# evalboard_v2.net
KiCad netlist of a schematic drawn in EAGLE
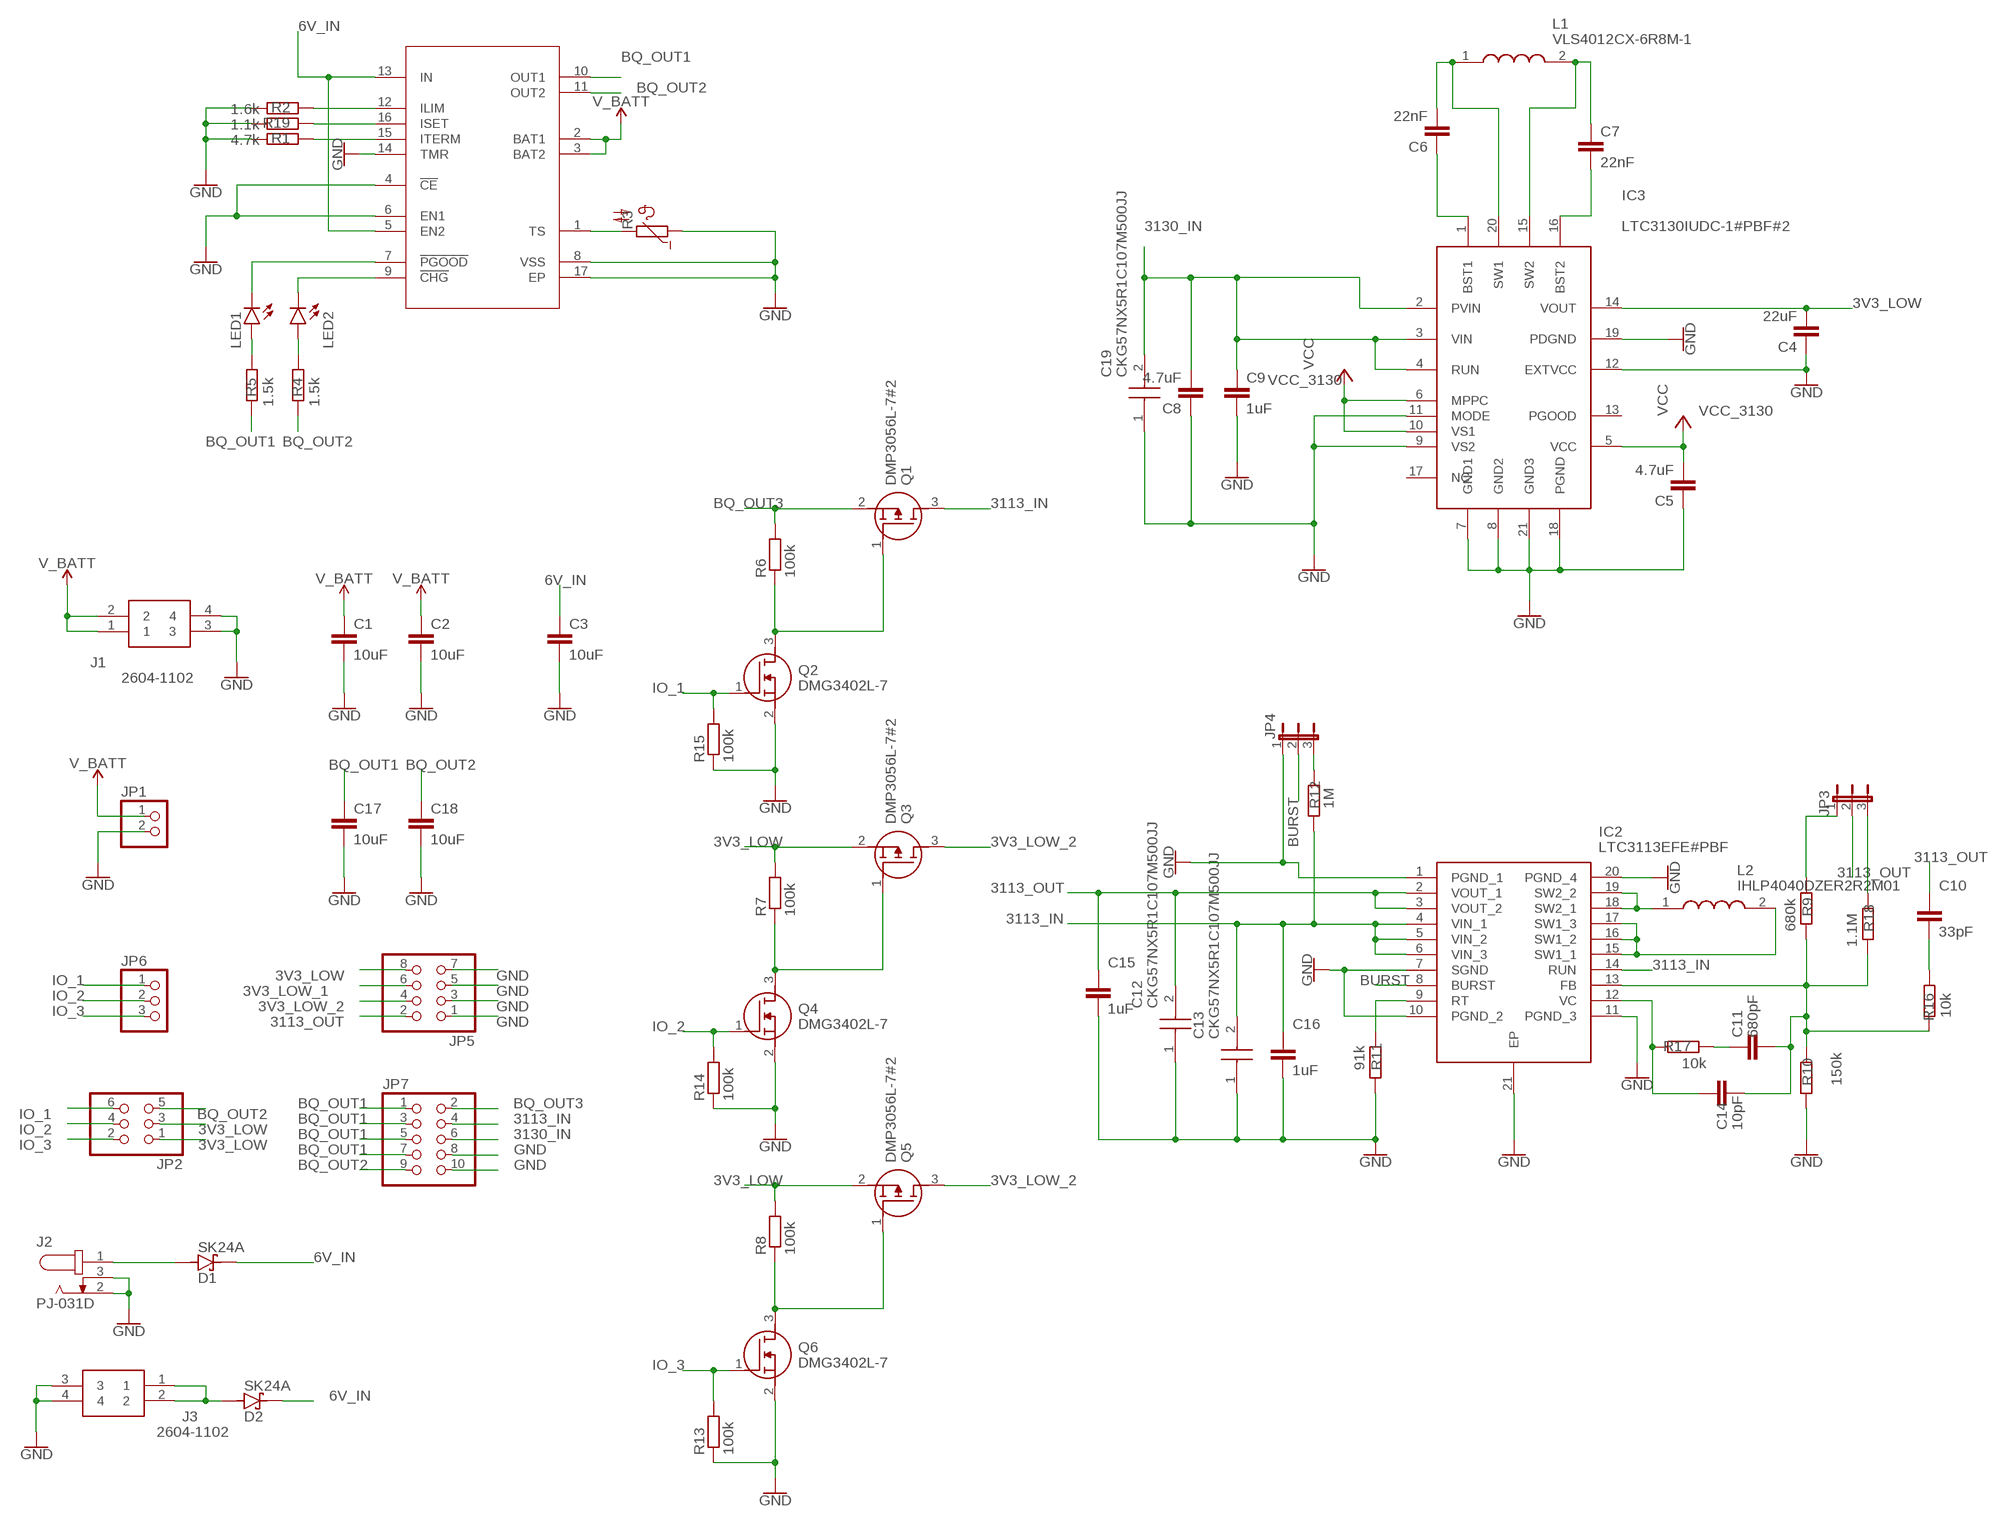
[diagram p0: schematic, sheet 1]

(export (version "E")
  (design (tool "Eeschema 10.0.6"))
  (components
    (comp (ref "C1")
      (value "10uF")
      (footprint "eagle-import:C1210")
      (libsource (lib "eagle-import") (part "C-EUC1210"))
    )
    (comp (ref "C2")
      (value "10uF")
      (footprint "eagle-import:C1210")
      (libsource (lib "eagle-import") (part "C-EUC1210"))
    )
    (comp (ref "C3")
      (value "10uF")
      (footprint "eagle-import:C1210")
      (libsource (lib "eagle-import") (part "C-EUC1210"))
    )
    (comp (ref "C4")
      (value "22uF")
      (footprint "eagle-import:C1210")
      (libsource (lib "eagle-import") (part "C-EUC1210"))
    )
    (comp (ref "C5")
      (value "4.7uF")
      (footprint "eagle-import:C1210")
      (libsource (lib "eagle-import") (part "C-EUC1210"))
    )
    (comp (ref "C6")
      (value "22nF")
      (footprint "eagle-import:C0603")
      (libsource (lib "eagle-import") (part "C-EUC0603"))
    )
    (comp (ref "C7")
      (value "22nF")
      (footprint "eagle-import:C0603")
      (libsource (lib "eagle-import") (part "C-EUC0603"))
    )
    (comp (ref "C8")
      (value "4.7uF")
      (footprint "eagle-import:C1210")
      (libsource (lib "eagle-import") (part "C-EUC1210"))
    )
    (comp (ref "C9")
      (value "1uF")
      (footprint "eagle-import:C0603")
      (libsource (lib "eagle-import") (part "C-EUC0603"))
    )
    (comp (ref "C10")
      (value "33pF")
      (footprint "eagle-import:C0603")
      (libsource (lib "eagle-import") (part "C-EUC0603"))
    )
    (comp (ref "C11")
      (value "680pF")
      (footprint "eagle-import:C0603")
      (libsource (lib "eagle-import") (part "C-EUC0603"))
    )
    (comp (ref "C12")
      (value "CKG57NX5R1C107M500JJ")
      (footprint "eagle-import:CAPC6050X550N")
      (fields (field (name "MOUSER_PART_NUMBER") "810-CKG57NX5R1C107MJ"))
      (libsource (lib "eagle-import") (part "CKG57NX5R1C107M500JJ"))
    )
    (comp (ref "C13")
      (value "CKG57NX5R1C107M500JJ")
      (footprint "eagle-import:CAPC6050X550N")
      (fields (field (name "MOUSER_PART_NUMBER") "810-CKG57NX5R1C107MJ"))
      (libsource (lib "eagle-import") (part "CKG57NX5R1C107M500JJ"))
    )
    (comp (ref "C14")
      (value "10pF")
      (footprint "eagle-import:C0603")
      (libsource (lib "eagle-import") (part "C-EUC0603"))
    )
    (comp (ref "C15")
      (value "1uF")
      (footprint "eagle-import:C0603")
      (libsource (lib "eagle-import") (part "C-EUC0603"))
    )
    (comp (ref "C16")
      (value "1uF")
      (footprint "eagle-import:C0603")
      (libsource (lib "eagle-import") (part "C-EUC0603"))
    )
    (comp (ref "C17")
      (value "10uF")
      (footprint "eagle-import:C1210")
      (libsource (lib "eagle-import") (part "C-EUC1210"))
    )
    (comp (ref "C18")
      (value "10uF")
      (footprint "eagle-import:C1210")
      (libsource (lib "eagle-import") (part "C-EUC1210"))
    )
    (comp (ref "C19")
      (value "CKG57NX5R1C107M500JJ")
      (footprint "eagle-import:CAPC6050X550N")
      (fields (field (name "MOUSER_PART_NUMBER") "810-CKG57NX5R1C107MJ"))
      (libsource (lib "eagle-import") (part "CKG57NX5R1C107M500JJ"))
    )
    (comp (ref "D1")
      (value "SK24A")
      (footprint "eagle-import:DIOM4325X250N")
      (fields (field (name "DIGI-KEY_PART_NUMBER") "1655-SK24ATR-ND") (field (name "MF") "SMC Diode"))
      (libsource (lib "eagle-import") (part "SK24A"))
    )
    (comp (ref "D2")
      (value "SK24A")
      (footprint "eagle-import:DIOM4325X250N")
      (fields (field (name "DIGI-KEY_PART_NUMBER") "1655-SK24ATR-ND") (field (name "MF") "SMC Diode"))
      (libsource (lib "eagle-import") (part "SK24A"))
    )
    (comp (ref "IC1")
      (value "BQ24074")
      (footprint "eagle-import:QFN50P300X300X100-17N")
      (libsource (lib "eagle-import") (part "BQ24074"))
    )
    (comp (ref "IC2")
      (value "LTC3113EFE#PBF")
      (footprint "eagle-import:SOP65P640X120-21N")
      (fields (field (name "MOUSER_PART_NUMBER") "584-LTC3113EFE#PBF"))
      (libsource (lib "eagle-import") (part "LTC3113EFE#PBF"))
    )
    (comp (ref "IC3")
      (value "LTC3130IUDC-1#PBF#2")
      (footprint "eagle-import:QFN50P300X400X80-21N")
      (fields (field (name "MANUFACTURER_PART_NUMBER") "LTC3130IUDC-1#PBF"))
      (libsource (lib "eagle-import") (part "LTC3130IUDC-1#PBF#2"))
    )
    (comp (ref "J1")
      (value "2604-1102")
      (footprint "eagle-import:26041102")
      (libsource (lib "eagle-import") (part "2604-1102"))
    )
    (comp (ref "J2")
      (value "PJ-031D")
      (footprint "eagle-import:CUI_PJ-031D")
      (fields (field (name "MF") "CUI Devices"))
      (libsource (lib "eagle-import") (part "PJ-031D"))
    )
    (comp (ref "J3")
      (value "2604-1102")
      (footprint "eagle-import:26041102")
      (libsource (lib "eagle-import") (part "2604-1102"))
    )
    (comp (ref "JP1")
      (value "PINHD-1X2")
      (footprint "eagle-import:1X02")
      (libsource (lib "eagle-import") (part "PINHD-1X2"))
    )
    (comp (ref "JP2")
      (value "PINHD-2X3")
      (footprint "eagle-import:2X03")
      (libsource (lib "eagle-import") (part "PINHD-2X3"))
    )
    (comp (ref "JP3")
      (value "JP2E")
      (footprint "eagle-import:JP2")
      (libsource (lib "eagle-import") (part "JP2E"))
    )
    (comp (ref "JP4")
      (value "JP2E")
      (footprint "eagle-import:JP2")
      (libsource (lib "eagle-import") (part "JP2E"))
    )
    (comp (ref "JP5")
      (value "PINHD-2X4")
      (footprint "eagle-import:2X04")
      (libsource (lib "eagle-import") (part "PINHD-2X4"))
    )
    (comp (ref "JP6")
      (value "PINHD-1X3")
      (footprint "eagle-import:1X03")
      (libsource (lib "eagle-import") (part "PINHD-1X3"))
    )
    (comp (ref "JP7")
      (value "PINHD-2X5")
      (footprint "eagle-import:2X05")
      (libsource (lib "eagle-import") (part "PINHD-2X5"))
    )
    (comp (ref "L1")
      (value "VLS4012CX-6R8M-1")
      (footprint "eagle-import:VLS4012")
      (libsource (lib "eagle-import") (part "VLS4012CX-6R8M-1"))
    )
    (comp (ref "L2")
      (value "IHLP4040DZER2R2M01")
      (footprint "eagle-import:INDPM108102X400N")
      (fields (field (name "MOUSER_PART_NUMBER") "70-IHLP4040DZER2R2M0"))
      (libsource (lib "eagle-import") (part "IHLP4040DZER2R2M01"))
    )
    (comp (ref "LED1")
      (value "LEDCHIP-LED0603")
      (footprint "eagle-import:CHIP-LED0603")
      (libsource (lib "eagle-import") (part "LEDCHIP-LED0603"))
    )
    (comp (ref "LED2")
      (value "LEDCHIP-LED0603")
      (footprint "eagle-import:CHIP-LED0603")
      (libsource (lib "eagle-import") (part "LEDCHIP-LED0603"))
    )
    (comp (ref "Q1")
      (value "DMP3056L-7#2")
      (footprint "eagle-import:SOT96P240X100-3N")
      (fields
        (field (name "ARROW_PART_NUMBER") "DMP3056L-7")
        (field (name "MOUSER_PART_NUMBER") "621-DMP3056L-7")
      )
      (libsource (lib "eagle-import") (part "DMP3056L-7#2"))
    )
    (comp (ref "Q2")
      (value "DMG3402L-7")
      (footprint "eagle-import:SOT96P240X110-3N")
      (fields (field (name "MOUSER_PART_NUMBER") "621-DMG3402L-7"))
      (libsource (lib "eagle-import") (part "DMG3402L-7"))
    )
    (comp (ref "Q3")
      (value "DMP3056L-7#2")
      (footprint "eagle-import:SOT96P240X100-3N")
      (fields
        (field (name "ARROW_PART_NUMBER") "DMP3056L-7")
        (field (name "MOUSER_PART_NUMBER") "621-DMP3056L-7")
      )
      (libsource (lib "eagle-import") (part "DMP3056L-7#2"))
    )
    (comp (ref "Q4")
      (value "DMG3402L-7")
      (footprint "eagle-import:SOT96P240X110-3N")
      (fields (field (name "MOUSER_PART_NUMBER") "621-DMG3402L-7"))
      (libsource (lib "eagle-import") (part "DMG3402L-7"))
    )
    (comp (ref "Q5")
      (value "DMP3056L-7#2")
      (footprint "eagle-import:SOT96P240X100-3N")
      (fields
        (field (name "ARROW_PART_NUMBER") "DMP3056L-7")
        (field (name "MOUSER_PART_NUMBER") "621-DMP3056L-7")
      )
      (libsource (lib "eagle-import") (part "DMP3056L-7#2"))
    )
    (comp (ref "Q6")
      (value "DMG3402L-7")
      (footprint "eagle-import:SOT96P240X110-3N")
      (fields (field (name "MOUSER_PART_NUMBER") "621-DMG3402L-7"))
      (libsource (lib "eagle-import") (part "DMG3402L-7"))
    )
    (comp (ref "R1")
      (value "4.7k")
      (footprint "eagle-import:R0603")
      (libsource (lib "eagle-import") (part "R-EU_R0603"))
    )
    (comp (ref "R2")
      (value "1.6k")
      (footprint "eagle-import:R0603")
      (libsource (lib "eagle-import") (part "R-EU_R0603"))
    )
    (comp (ref "R3")
      (value "10k")
      (footprint "eagle-import:P640")
      (libsource (lib "eagle-import") (part "NTC640"))
    )
    (comp (ref "R4")
      (value "1.5k")
      (footprint "eagle-import:R0603")
      (libsource (lib "eagle-import") (part "R-EU_R0603"))
    )
    (comp (ref "R5")
      (value "1.5k")
      (footprint "eagle-import:R0603")
      (libsource (lib "eagle-import") (part "R-EU_R0603"))
    )
    (comp (ref "R6")
      (value "100k")
      (footprint "eagle-import:R0603")
      (libsource (lib "eagle-import") (part "R-EU_R0603"))
    )
    (comp (ref "R7")
      (value "100k")
      (footprint "eagle-import:R0603")
      (libsource (lib "eagle-import") (part "R-EU_R0603"))
    )
    (comp (ref "R8")
      (value "100k")
      (footprint "eagle-import:R0603")
      (libsource (lib "eagle-import") (part "R-EU_R0603"))
    )
    (comp (ref "R9")
      (value "680k")
      (footprint "eagle-import:R0603")
      (libsource (lib "eagle-import") (part "R-EU_R0603"))
    )
    (comp (ref "R10")
      (value "150k")
      (footprint "eagle-import:R0603")
      (libsource (lib "eagle-import") (part "R-EU_R0603"))
    )
    (comp (ref "R11")
      (value "91k")
      (footprint "eagle-import:R0603")
      (libsource (lib "eagle-import") (part "R-EU_R0603"))
    )
    (comp (ref "R12")
      (value "1M")
      (footprint "eagle-import:R0603")
      (libsource (lib "eagle-import") (part "R-EU_R0603"))
    )
    (comp (ref "R13")
      (value "100k")
      (footprint "eagle-import:R0603")
      (libsource (lib "eagle-import") (part "R-EU_R0603"))
    )
    (comp (ref "R14")
      (value "100k")
      (footprint "eagle-import:R0603")
      (libsource (lib "eagle-import") (part "R-EU_R0603"))
    )
    (comp (ref "R15")
      (value "100k")
      (footprint "eagle-import:R0603")
      (libsource (lib "eagle-import") (part "R-EU_R0603"))
    )
    (comp (ref "R16")
      (value "10k")
      (footprint "eagle-import:R0603")
      (libsource (lib "eagle-import") (part "R-EU_R0603"))
    )
    (comp (ref "R17")
      (value "10k")
      (footprint "eagle-import:R0603")
      (libsource (lib "eagle-import") (part "R-EU_R0603"))
    )
    (comp (ref "R18")
      (value "1.1M")
      (footprint "eagle-import:R0603")
      (libsource (lib "eagle-import") (part "R-EU_R0603"))
    )
    (comp (ref "R19")
      (value "1.1k")
      (footprint "eagle-import:R0603")
      (libsource (lib "eagle-import") (part "R-EU_R0603"))
    )
  )
  (nets
    (net (code "1") (name "/3V3_LOW") (class "Default")
      (node (ref "C4") (pin "2") (pinfunction "2_2") (pintype "passive"))
      (node (ref "IC3") (pin "14") (pinfunction "VOUT_14") (pintype "output"))
      (node (ref "JP2") (pin "1") (pinfunction "1_1") (pintype "passive"))
      (node (ref "JP2") (pin "3") (pinfunction "3_3") (pintype "passive"))
      (node (ref "JP5") (pin "8") (pinfunction "8_8") (pintype "passive"))
      (node (ref "Q3") (pin "2") (pinfunction "S_2") (pintype "bidirectional"))
      (node (ref "Q5") (pin "2") (pinfunction "S_2") (pintype "bidirectional"))
      (node (ref "R7") (pin "2") (pinfunction "2_2") (pintype "passive"))
      (node (ref "R8") (pin "2") (pinfunction "2_2") (pintype "passive"))
    )
    (net (code "2") (name "/3V3_LOW_1") (class "Default")
      (node (ref "JP5") (pin "6") (pinfunction "6_6") (pintype "passive"))
    )
    (net (code "3") (name "/3V3_LOW_2") (class "Default")
      (node (ref "JP5") (pin "4") (pinfunction "4_4") (pintype "passive"))
      (node (ref "Q3") (pin "3") (pinfunction "D_3") (pintype "bidirectional"))
      (node (ref "Q5") (pin "3") (pinfunction "D_3") (pintype "bidirectional"))
    )
    (net (code "4") (name "/6V_IN") (class "Default")
      (node (ref "C3") (pin "1") (pinfunction "1_1") (pintype "passive"))
      (node (ref "D1") (pin "C") (pinfunction "K_C") (pintype "passive"))
      (node (ref "D2") (pin "C") (pinfunction "K_C") (pintype "passive"))
      (node (ref "IC1") (pin "13") (pinfunction "IN_13") (pintype "bidirectional"))
      (node (ref "IC1") (pin "5") (pinfunction "EN2_5") (pintype "bidirectional"))
    )
    (net (code "5") (name "/3113_IN") (class "Default")
      (node (ref "C13") (pin "2") (pinfunction "2_2") (pintype "bidirectional"))
      (node (ref "C16") (pin "1") (pinfunction "1_1") (pintype "passive"))
      (node (ref "IC2") (pin "14") (pinfunction "RUN_14") (pintype "bidirectional"))
      (node (ref "IC2") (pin "4") (pinfunction "VIN_1_4") (pintype "bidirectional"))
      (node (ref "IC2") (pin "5") (pinfunction "VIN_2_5") (pintype "bidirectional"))
      (node (ref "IC2") (pin "6") (pinfunction "VIN_3_6") (pintype "bidirectional"))
      (node (ref "JP7") (pin "4") (pinfunction "4_4") (pintype "passive"))
      (node (ref "Q1") (pin "3") (pinfunction "D_3") (pintype "bidirectional"))
      (node (ref "R12") (pin "1") (pinfunction "1_1") (pintype "passive"))
    )
    (net (code "6") (name "/3113_OUT") (class "Default")
      (node (ref "C10") (pin "1") (pinfunction "1_1") (pintype "passive"))
      (node (ref "C12") (pin "2") (pinfunction "2_2") (pintype "bidirectional"))
      (node (ref "C15") (pin "1") (pinfunction "1_1") (pintype "passive"))
      (node (ref "IC2") (pin "2") (pinfunction "VOUT_1_2") (pintype "bidirectional"))
      (node (ref "IC2") (pin "3") (pinfunction "VOUT_2_3") (pintype "bidirectional"))
      (node (ref "JP3") (pin "2") (pinfunction "2_2") (pintype "passive"))
      (node (ref "JP5") (pin "2") (pinfunction "2_2") (pintype "passive"))
    )
    (net (code "7") (name "/3130_IN") (class "Default")
      (node (ref "C19") (pin "2") (pinfunction "2_2") (pintype "bidirectional"))
      (node (ref "C8") (pin "2") (pinfunction "2_2") (pintype "passive"))
      (node (ref "C9") (pin "1") (pinfunction "1_1") (pintype "passive"))
      (node (ref "IC3") (pin "2") (pinfunction "PVIN_2") (pintype "input"))
      (node (ref "IC3") (pin "3") (pinfunction "VIN_3") (pintype "input"))
      (node (ref "IC3") (pin "4") (pinfunction "RUN_4") (pintype "bidirectional"))
      (node (ref "JP7") (pin "6") (pinfunction "6_6") (pintype "passive"))
    )
    (net (code "8") (name "/BQ_OUT1") (class "Default")
      (node (ref "C17") (pin "1") (pinfunction "1_1") (pintype "passive"))
      (node (ref "IC1") (pin "10") (pinfunction "OUT1_10") (pintype "bidirectional"))
      (node (ref "JP7") (pin "1") (pinfunction "1_1") (pintype "passive"))
      (node (ref "JP7") (pin "3") (pinfunction "3_3") (pintype "passive"))
      (node (ref "JP7") (pin "5") (pinfunction "5_5") (pintype "passive"))
      (node (ref "JP7") (pin "7") (pinfunction "7_7") (pintype "passive"))
      (node (ref "R5") (pin "2") (pinfunction "2_2") (pintype "passive"))
    )
    (net (code "9") (name "/BQ_OUT2") (class "Default")
      (node (ref "C18") (pin "1") (pinfunction "1_1") (pintype "passive"))
      (node (ref "IC1") (pin "11") (pinfunction "OUT2_11") (pintype "bidirectional"))
      (node (ref "JP2") (pin "5") (pinfunction "5_5") (pintype "passive"))
      (node (ref "JP7") (pin "9") (pinfunction "9_9") (pintype "passive"))
      (node (ref "R4") (pin "2") (pinfunction "2_2") (pintype "passive"))
    )
    (net (code "10") (name "/BQ_OUT3") (class "Default")
      (node (ref "JP7") (pin "2") (pinfunction "2_2") (pintype "passive"))
      (node (ref "Q1") (pin "2") (pinfunction "S_2") (pintype "bidirectional"))
      (node (ref "R6") (pin "2") (pinfunction "2_2") (pintype "passive"))
    )
    (net (code "11") (name "/BURST") (class "Default")
      (node (ref "IC2") (pin "8") (pinfunction "BURST_8") (pintype "bidirectional"))
      (node (ref "JP4") (pin "2") (pinfunction "2_2") (pintype "passive"))
    )
    (net (code "12") (name "/IO_1") (class "Default")
      (node (ref "JP2") (pin "6") (pinfunction "6_6") (pintype "passive"))
      (node (ref "JP6") (pin "1") (pinfunction "1_1") (pintype "passive"))
      (node (ref "Q2") (pin "1") (pinfunction "G_1") (pintype "bidirectional"))
      (node (ref "R15") (pin "2") (pinfunction "2_2") (pintype "passive"))
    )
    (net (code "13") (name "/IO_2") (class "Default")
      (node (ref "JP2") (pin "4") (pinfunction "4_4") (pintype "passive"))
      (node (ref "JP6") (pin "2") (pinfunction "2_2") (pintype "passive"))
      (node (ref "Q4") (pin "1") (pinfunction "G_1") (pintype "bidirectional"))
      (node (ref "R14") (pin "2") (pinfunction "2_2") (pintype "passive"))
    )
    (net (code "14") (name "/IO_3") (class "Default")
      (node (ref "JP2") (pin "2") (pinfunction "2_2") (pintype "passive"))
      (node (ref "JP6") (pin "3") (pinfunction "3_3") (pintype "passive"))
      (node (ref "Q6") (pin "1") (pinfunction "G_1") (pintype "bidirectional"))
      (node (ref "R13") (pin "2") (pinfunction "2_2") (pintype "passive"))
    )
    (net (code "15") (name "GND") (class "Default")
      (node (ref "C1") (pin "2") (pinfunction "2_2") (pintype "passive"))
      (node (ref "C12") (pin "1") (pinfunction "1_1") (pintype "bidirectional"))
      (node (ref "C13") (pin "1") (pinfunction "1_1") (pintype "bidirectional"))
      (node (ref "C15") (pin "2") (pinfunction "2_2") (pintype "passive"))
      (node (ref "C16") (pin "2") (pinfunction "2_2") (pintype "passive"))
      (node (ref "C17") (pin "2") (pinfunction "2_2") (pintype "passive"))
      (node (ref "C18") (pin "2") (pinfunction "2_2") (pintype "passive"))
      (node (ref "C19") (pin "1") (pinfunction "1_1") (pintype "bidirectional"))
      (node (ref "C2") (pin "2") (pinfunction "2_2") (pintype "passive"))
      (node (ref "C3") (pin "2") (pinfunction "2_2") (pintype "passive"))
      (node (ref "C4") (pin "1") (pinfunction "1_1") (pintype "passive"))
      (node (ref "C5") (pin "1") (pinfunction "1_1") (pintype "passive"))
      (node (ref "C8") (pin "1") (pinfunction "1_1") (pintype "passive"))
      (node (ref "C9") (pin "2") (pinfunction "2_2") (pintype "passive"))
      (node (ref "IC1") (pin "14") (pinfunction "TMR_14") (pintype "bidirectional"))
      (node (ref "IC1") (pin "17") (pinfunction "EP_17") (pintype "bidirectional"))
      (node (ref "IC1") (pin "4") (pinfunction "~{CE}_4") (pintype "bidirectional"))
      (node (ref "IC1") (pin "6") (pinfunction "EN1_6") (pintype "bidirectional"))
      (node (ref "IC1") (pin "8") (pinfunction "VSS_8") (pintype "bidirectional"))
      (node (ref "IC2") (pin "1") (pinfunction "PGND_1_1") (pintype "bidirectional"))
      (node (ref "IC2") (pin "10") (pinfunction "PGND_2_10") (pintype "bidirectional"))
      (node (ref "IC2") (pin "11") (pinfunction "PGND_3_11") (pintype "bidirectional"))
      (node (ref "IC2") (pin "20") (pinfunction "PGND_4_20") (pintype "bidirectional"))
      (node (ref "IC2") (pin "21") (pinfunction "EP_21") (pintype "bidirectional"))
      (node (ref "IC2") (pin "7") (pinfunction "SGND_7") (pintype "bidirectional"))
      (node (ref "IC3") (pin "11") (pinfunction "MODE_11") (pintype "bidirectional"))
      (node (ref "IC3") (pin "12") (pinfunction "EXTVCC_12") (pintype "bidirectional"))
      (node (ref "IC3") (pin "18") (pinfunction "PGND_18") (pintype "bidirectional"))
      (node (ref "IC3") (pin "19") (pinfunction "PDGND_19") (pintype "bidirectional"))
      (node (ref "IC3") (pin "21") (pinfunction "GND3_21") (pintype "bidirectional"))
      (node (ref "IC3") (pin "7") (pinfunction "GND1_7") (pintype "bidirectional"))
      (node (ref "IC3") (pin "8") (pinfunction "GND2_8") (pintype "bidirectional"))
      (node (ref "IC3") (pin "9") (pinfunction "VS2_9") (pintype "bidirectional"))
      (node (ref "J1") (pin "3") (pinfunction "3_3") (pintype "bidirectional"))
      (node (ref "J1") (pin "4") (pinfunction "4_4") (pintype "bidirectional"))
      (node (ref "J2") (pin "2") (pinfunction "2_2") (pintype "passive"))
      (node (ref "J2") (pin "3") (pinfunction "3_3") (pintype "passive"))
      (node (ref "J3") (pin "3") (pinfunction "3_3") (pintype "bidirectional"))
      (node (ref "J3") (pin "4") (pinfunction "4_4") (pintype "bidirectional"))
      (node (ref "JP1") (pin "2") (pinfunction "2_2") (pintype "passive"))
      (node (ref "JP4") (pin "1") (pinfunction "1_1") (pintype "passive"))
      (node (ref "JP5") (pin "1") (pinfunction "1_1") (pintype "passive"))
      (node (ref "JP5") (pin "3") (pinfunction "3_3") (pintype "passive"))
      (node (ref "JP5") (pin "5") (pinfunction "5_5") (pintype "passive"))
      (node (ref "JP5") (pin "7") (pinfunction "7_7") (pintype "passive"))
      (node (ref "JP7") (pin "10") (pinfunction "10_10") (pintype "passive"))
      (node (ref "JP7") (pin "8") (pinfunction "8_8") (pintype "passive"))
      (node (ref "Q2") (pin "2") (pinfunction "S_2") (pintype "bidirectional"))
      (node (ref "Q4") (pin "2") (pinfunction "S_2") (pintype "bidirectional"))
      (node (ref "Q6") (pin "2") (pinfunction "S_2") (pintype "bidirectional"))
      (node (ref "R1") (pin "2") (pinfunction "2_2") (pintype "passive"))
      (node (ref "R10") (pin "1") (pinfunction "1_1") (pintype "passive"))
      (node (ref "R11") (pin "1") (pinfunction "1_1") (pintype "passive"))
      (node (ref "R13") (pin "1") (pinfunction "1_1") (pintype "passive"))
      (node (ref "R14") (pin "1") (pinfunction "1_1") (pintype "passive"))
      (node (ref "R15") (pin "1") (pinfunction "1_1") (pintype "passive"))
      (node (ref "R19") (pin "2") (pinfunction "2_2") (pintype "passive"))
      (node (ref "R2") (pin "2") (pinfunction "2_2") (pintype "passive"))
      (node (ref "R3") (pin "1") (pinfunction "1_1") (pintype "passive"))
    )
    (net (code "16") (name "Net-(C10-Pad2)") (class "Default")
      (node (ref "C10") (pin "2") (pinfunction "2_2") (pintype "passive"))
      (node (ref "R16") (pin "1") (pinfunction "1_1") (pintype "passive"))
    )
    (net (code "17") (name "Net-(C11-Pad1)") (class "Default")
      (node (ref "C11") (pin "1") (pinfunction "1_1") (pintype "passive"))
      (node (ref "R17") (pin "1") (pinfunction "1_1") (pintype "passive"))
    )
    (net (code "18") (name "Net-(D1-PadA)") (class "Default")
      (node (ref "D1") (pin "A") (pinfunction "A_A") (pintype "passive"))
      (node (ref "J2") (pin "1") (pinfunction "1_1") (pintype "passive"))
    )
    (net (code "19") (name "Net-(D2-PadA)") (class "Default")
      (node (ref "D2") (pin "A") (pinfunction "A_A") (pintype "passive"))
      (node (ref "J3") (pin "1") (pinfunction "1_1") (pintype "bidirectional"))
      (node (ref "J3") (pin "2") (pinfunction "2_2") (pintype "bidirectional"))
    )
    (net (code "20") (name "Net-(IC1-ILIM)") (class "Default")
      (node (ref "IC1") (pin "12") (pinfunction "ILIM_12") (pintype "bidirectional"))
      (node (ref "R2") (pin "1") (pinfunction "1_1") (pintype "passive"))
    )
    (net (code "21") (name "Net-(IC1-ISET)") (class "Default")
      (node (ref "IC1") (pin "16") (pinfunction "ISET_16") (pintype "bidirectional"))
      (node (ref "R19") (pin "1") (pinfunction "1_1") (pintype "passive"))
    )
    (net (code "22") (name "Net-(IC1-ITERM)") (class "Default")
      (node (ref "IC1") (pin "15") (pinfunction "ITERM_15") (pintype "bidirectional"))
      (node (ref "R1") (pin "1") (pinfunction "1_1") (pintype "passive"))
    )
    (net (code "23") (name "Net-(IC1-TS)") (class "Default")
      (node (ref "IC1") (pin "1") (pinfunction "TS_1") (pintype "bidirectional"))
      (node (ref "R3") (pin "2") (pinfunction "2_2") (pintype "passive"))
    )
    (net (code "24") (name "Net-(IC1-~{CHG})") (class "Default")
      (node (ref "IC1") (pin "9") (pinfunction "~{CHG}_9") (pintype "bidirectional"))
      (node (ref "LED2") (pin "C") (pinfunction "C_C") (pintype "passive"))
    )
    (net (code "25") (name "Net-(IC1-~{PGOOD})") (class "Default")
      (node (ref "IC1") (pin "7") (pinfunction "~{PGOOD}_7") (pintype "bidirectional"))
      (node (ref "LED1") (pin "C") (pinfunction "C_C") (pintype "passive"))
    )
    (net (code "26") (name "Net-(IC2-FB)") (class "Default")
      (node (ref "C11") (pin "2") (pinfunction "2_2") (pintype "passive"))
      (node (ref "C14") (pin "2") (pinfunction "2_2") (pintype "passive"))
      (node (ref "IC2") (pin "13") (pinfunction "FB_13") (pintype "bidirectional"))
      (node (ref "R10") (pin "2") (pinfunction "2_2") (pintype "passive"))
      (node (ref "R16") (pin "2") (pinfunction "2_2") (pintype "passive"))
      (node (ref "R18") (pin "1") (pinfunction "1_1") (pintype "passive"))
      (node (ref "R9") (pin "1") (pinfunction "1_1") (pintype "passive"))
    )
    (net (code "27") (name "Net-(IC2-RT)") (class "Default")
      (node (ref "IC2") (pin "9") (pinfunction "RT_9") (pintype "bidirectional"))
      (node (ref "R11") (pin "2") (pinfunction "2_2") (pintype "passive"))
    )
    (net (code "28") (name "Net-(IC2-SW1_1)") (class "Default")
      (node (ref "IC2") (pin "15") (pinfunction "SW1_1_15") (pintype "bidirectional"))
      (node (ref "IC2") (pin "16") (pinfunction "SW1_2_16") (pintype "bidirectional"))
      (node (ref "IC2") (pin "17") (pinfunction "SW1_3_17") (pintype "bidirectional"))
      (node (ref "L2") (pin "2") (pinfunction "2_2") (pintype "bidirectional"))
    )
    (net (code "29") (name "Net-(IC2-SW2_1)") (class "Default")
      (node (ref "IC2") (pin "18") (pinfunction "SW2_1_18") (pintype "bidirectional"))
      (node (ref "IC2") (pin "19") (pinfunction "SW2_2_19") (pintype "bidirectional"))
      (node (ref "L2") (pin "1") (pinfunction "1_1") (pintype "bidirectional"))
    )
    (net (code "30") (name "Net-(IC2-VC)") (class "Default")
      (node (ref "C14") (pin "1") (pinfunction "1_1") (pintype "passive"))
      (node (ref "IC2") (pin "12") (pinfunction "VC_12") (pintype "bidirectional"))
      (node (ref "R17") (pin "2") (pinfunction "2_2") (pintype "passive"))
    )
    (net (code "31") (name "Net-(IC3-BST1)") (class "Default")
      (node (ref "C6") (pin "1") (pinfunction "1_1") (pintype "passive"))
      (node (ref "IC3") (pin "1") (pinfunction "BST1_1") (pintype "bidirectional"))
    )
    (net (code "32") (name "Net-(IC3-BST2)") (class "Default")
      (node (ref "C7") (pin "2") (pinfunction "2_2") (pintype "passive"))
      (node (ref "IC3") (pin "16") (pinfunction "BST2_16") (pintype "bidirectional"))
    )
    (net (code "33") (name "Net-(IC3-SW1)") (class "Default")
      (node (ref "C6") (pin "2") (pinfunction "2_2") (pintype "passive"))
      (node (ref "IC3") (pin "20") (pinfunction "SW1_20") (pintype "bidirectional"))
      (node (ref "L1") (pin "1") (pinfunction "1_1") (pintype "bidirectional"))
    )
    (net (code "34") (name "Net-(IC3-SW2)") (class "Default")
      (node (ref "C7") (pin "1") (pinfunction "1_1") (pintype "passive"))
      (node (ref "IC3") (pin "15") (pinfunction "SW2_15") (pintype "bidirectional"))
      (node (ref "L1") (pin "2") (pinfunction "2_2") (pintype "bidirectional"))
    )
    (net (code "35") (name "Net-(JP3-Pad1)") (class "Default")
      (node (ref "JP3") (pin "1") (pinfunction "1_1") (pintype "passive"))
      (node (ref "R9") (pin "2") (pinfunction "2_2") (pintype "passive"))
    )
    (net (code "36") (name "Net-(JP3-Pad3)") (class "Default")
      (node (ref "JP3") (pin "3") (pinfunction "3_3") (pintype "passive"))
      (node (ref "R18") (pin "2") (pinfunction "2_2") (pintype "passive"))
    )
    (net (code "37") (name "Net-(JP4-Pad3)") (class "Default")
      (node (ref "JP4") (pin "3") (pinfunction "3_3") (pintype "passive"))
      (node (ref "R12") (pin "2") (pinfunction "2_2") (pintype "passive"))
    )
    (net (code "38") (name "Net-(LED1-PadA)") (class "Default")
      (node (ref "LED1") (pin "A") (pinfunction "A_A") (pintype "passive"))
      (node (ref "R5") (pin "1") (pinfunction "1_1") (pintype "passive"))
    )
    (net (code "39") (name "Net-(LED2-PadA)") (class "Default")
      (node (ref "LED2") (pin "A") (pinfunction "A_A") (pintype "passive"))
      (node (ref "R4") (pin "1") (pinfunction "1_1") (pintype "passive"))
    )
    (net (code "40") (name "Net-(Q1-G)") (class "Default")
      (node (ref "Q1") (pin "1") (pinfunction "G_1") (pintype "bidirectional"))
      (node (ref "Q2") (pin "3") (pinfunction "D_3") (pintype "bidirectional"))
      (node (ref "R6") (pin "1") (pinfunction "1_1") (pintype "passive"))
    )
    (net (code "41") (name "Net-(Q3-G)") (class "Default")
      (node (ref "Q3") (pin "1") (pinfunction "G_1") (pintype "bidirectional"))
      (node (ref "Q4") (pin "3") (pinfunction "D_3") (pintype "bidirectional"))
      (node (ref "R7") (pin "1") (pinfunction "1_1") (pintype "passive"))
    )
    (net (code "42") (name "Net-(Q5-G)") (class "Default")
      (node (ref "Q5") (pin "1") (pinfunction "G_1") (pintype "bidirectional"))
      (node (ref "Q6") (pin "3") (pinfunction "D_3") (pintype "bidirectional"))
      (node (ref "R8") (pin "1") (pinfunction "1_1") (pintype "passive"))
    )
    (net (code "43") (name "VCC") (class "Default")
      (node (ref "C5") (pin "2") (pinfunction "2_2") (pintype "passive"))
      (node (ref "IC3") (pin "10") (pinfunction "VS1_10") (pintype "bidirectional"))
      (node (ref "IC3") (pin "5") (pinfunction "VCC_5") (pintype "bidirectional"))
      (node (ref "IC3") (pin "6") (pinfunction "MPPC_6") (pintype "bidirectional"))
    )
    (net (code "44") (name "V_BATT") (class "Default")
      (node (ref "C1") (pin "1") (pinfunction "1_1") (pintype "passive"))
      (node (ref "C2") (pin "1") (pinfunction "1_1") (pintype "passive"))
      (node (ref "IC1") (pin "2") (pinfunction "BAT1_2") (pintype "bidirectional"))
      (node (ref "IC1") (pin "3") (pinfunction "BAT2_3") (pintype "bidirectional"))
      (node (ref "J1") (pin "1") (pinfunction "1_1") (pintype "bidirectional"))
      (node (ref "J1") (pin "2") (pinfunction "2_2") (pintype "bidirectional"))
      (node (ref "JP1") (pin "1") (pinfunction "1_1") (pintype "passive"))
    )
    (net (code "45") (name "unconnected-(IC3-NC-Pad17)") (class "Default")
      (node (ref "IC3") (pin "17") (pinfunction "NC_17") (pintype "bidirectional"))
    )
    (net (code "46") (name "unconnected-(IC3-PGOOD-Pad13)") (class "Default")
      (node (ref "IC3") (pin "13") (pinfunction "PGOOD_13") (pintype "bidirectional"))
    )
  )
)
